# map_5v_to_3v3.net
KiCad netlist of a schematic drawn in Altium Designer
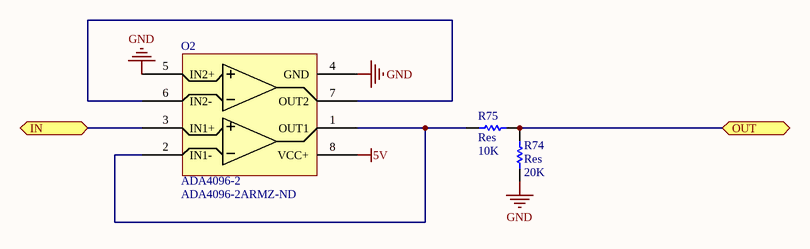
[diagram p0: map 5v to 3v3.SchDoc]

(export (version "E")
  (design (tool "Eeschema 10.0.6"))
  (components
    (comp (ref "O2")
      (value "ADA4096-2")
      (footprint "TSSOP8")
      (description "2 Op-Amps, 8-TSSOP, 32V Overvoltage Protection")
      (fields (field (name "SUPPLIER PART NUMBER 1") "ADA4096-2ARMZ-ND"))
      (libsource (lib "Operational Amplifiers") (part "ADA4096-2"))
    )
    (comp (ref "R74")
      (value "Res")
      (footprint "2012[0805]")
      (description "Surface Mount Resistor")
      (fields (field (name "ALTIUM_VALUE") "20K") (field (name "PUBLISHER") "Altium Limited"))
      (libsource (lib "Resistors") (part "Res"))
    )
    (comp (ref "R75")
      (value "Res")
      (footprint "2012[0805]")
      (description "Surface Mount Resistor")
      (fields (field (name "ALTIUM_VALUE") "10K") (field (name "PUBLISHER") "Altium Limited"))
      (libsource (lib "Resistors") (part "Res"))
    )
  )
  (nets
    (net (code "1") (name "/IN") (class "Default")
      (node (ref "O2") (pin "3") (pinfunction "IN1+_3") (pintype "passive"))
    )
    (net (code "2") (name "/OUT") (class "Default")
      (node (ref "R74") (pin "1") (pinfunction "1_1") (pintype "passive"))
      (node (ref "R75") (pin "1") (pinfunction "1_1") (pintype "passive"))
    )
    (net (code "3") (name "5V") (class "Default")
      (node (ref "O2") (pin "8") (pinfunction "VCC+_8") (pintype "passive"))
    )
    (net (code "4") (name "GND") (class "Default")
      (node (ref "O2") (pin "4") (pinfunction "GND_4") (pintype "passive"))
      (node (ref "O2") (pin "5") (pinfunction "IN2+_5") (pintype "passive"))
      (node (ref "R74") (pin "2") (pinfunction "2_2") (pintype "passive"))
    )
    (net (code "5") (name "Net-(O2-IN1-)") (class "Default")
      (node (ref "O2") (pin "1") (pinfunction "OUT1_1") (pintype "passive"))
      (node (ref "O2") (pin "2") (pinfunction "IN1-_2") (pintype "passive"))
      (node (ref "R75") (pin "2") (pinfunction "2_2") (pintype "passive"))
    )
    (net (code "6") (name "Net-(O2-IN2-)") (class "Default")
      (node (ref "O2") (pin "6") (pinfunction "IN2-_6") (pintype "passive"))
      (node (ref "O2") (pin "7") (pinfunction "OUT2_7") (pintype "passive"))
    )
  )
)
